# power_PCB_schematic.net
KiCad netlist of a schematic drawn in EAGLE
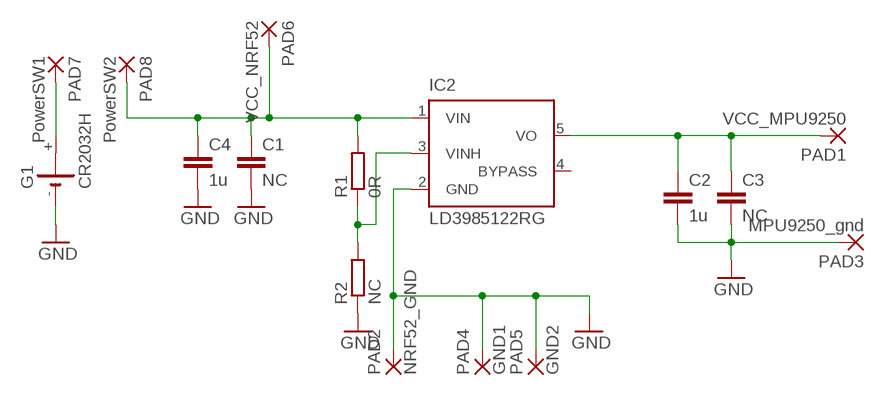
[diagram p0: schematic, sheet 1]

(export (version "E")
  (design (tool "Eeschema 10.0.6"))
  (components
    (comp (ref "C1")
      (value "NC")
      (footprint "eagle-import:C0805")
      (libsource (lib "eagle-import") (part "C-EUC0805"))
    )
    (comp (ref "C2")
      (value "1u")
      (footprint "eagle-import:C0805")
      (libsource (lib "eagle-import") (part "C-EUC0805"))
    )
    (comp (ref "C3")
      (value "NC")
      (footprint "eagle-import:C0805")
      (libsource (lib "eagle-import") (part "C-EUC0805"))
    )
    (comp (ref "C4")
      (value "1u")
      (footprint "eagle-import:C0805")
      (libsource (lib "eagle-import") (part "C-EUC0805"))
    )
    (comp (ref "G1")
      (value "CR2032H")
      (footprint "eagle-import:CR2032H")
      (libsource (lib "eagle-import") (part "CR2032H"))
    )
    (comp (ref "IC2")
      (value "LD3985122RG")
      (footprint "eagle-import:TSOT23-5L")
      (libsource (lib "eagle-import") (part "LD3985G122R"))
    )
    (comp (ref "PAD1")
      (value "VCC_MPU9250")
      (footprint "eagle-import:2,54_1,0")
      (libsource (lib "eagle-import") (part "2,54/1,0"))
    )
    (comp (ref "PAD2")
      (value "NRF52_GND")
      (footprint "eagle-import:2,54_1,0")
      (libsource (lib "eagle-import") (part "2,54/1,0"))
    )
    (comp (ref "PAD3")
      (value "MPU9250_gnd")
      (footprint "eagle-import:2,54_1,0")
      (libsource (lib "eagle-import") (part "2,54/1,0"))
    )
    (comp (ref "PAD4")
      (value "GND1")
      (footprint "eagle-import:2,54_1,0")
      (libsource (lib "eagle-import") (part "2,54/1,0"))
    )
    (comp (ref "PAD5")
      (value "GND2")
      (footprint "eagle-import:2,54_1,0")
      (libsource (lib "eagle-import") (part "2,54/1,0"))
    )
    (comp (ref "PAD6")
      (value "VCC_NRF52")
      (footprint "eagle-import:2,54_1,0")
      (libsource (lib "eagle-import") (part "2,54/1,0"))
    )
    (comp (ref "PAD7")
      (value "PowerSW1")
      (footprint "eagle-import:2,54_1,0")
      (libsource (lib "eagle-import") (part "2,54/1,0"))
    )
    (comp (ref "PAD8")
      (value "PowerSW2")
      (footprint "eagle-import:2,54_1,0")
      (libsource (lib "eagle-import") (part "2,54/1,0"))
    )
    (comp (ref "R1")
      (value "0R")
      (footprint "eagle-import:R1206")
      (libsource (lib "eagle-import") (part "R-EU_R1206"))
    )
    (comp (ref "R2")
      (value "NC")
      (footprint "eagle-import:R0603")
      (libsource (lib "eagle-import") (part "R-EU_R0603"))
    )
  )
  (nets
    (net (code "1") (name "GND") (class "Default")
      (node (ref "C1") (pin "2") (pinfunction "2_2") (pintype "passive"))
      (node (ref "C2") (pin "2") (pinfunction "2_2") (pintype "passive"))
      (node (ref "C3") (pin "2") (pinfunction "2_2") (pintype "passive"))
      (node (ref "C4") (pin "2") (pinfunction "2_2") (pintype "passive"))
      (node (ref "G1") (pin "-") (pinfunction "-_-") (pintype "passive"))
      (node (ref "IC2") (pin "2") (pinfunction "GND_2") (pintype "power_in"))
      (node (ref "PAD2") (pin "1") (pinfunction "P_1") (pintype "passive"))
      (node (ref "PAD3") (pin "1") (pinfunction "P_1") (pintype "passive"))
      (node (ref "PAD4") (pin "1") (pinfunction "P_1") (pintype "passive"))
      (node (ref "PAD5") (pin "1") (pinfunction "P_1") (pintype "passive"))
      (node (ref "R2") (pin "1") (pinfunction "1_1") (pintype "passive"))
    )
    (net (code "2") (name "Net-(IC2-VIN)") (class "Default")
      (node (ref "C1") (pin "1") (pinfunction "1_1") (pintype "passive"))
      (node (ref "C4") (pin "1") (pinfunction "1_1") (pintype "passive"))
      (node (ref "IC2") (pin "1") (pinfunction "VIN_1") (pintype "input"))
      (node (ref "PAD6") (pin "1") (pinfunction "P_1") (pintype "passive"))
      (node (ref "PAD8") (pin "1") (pinfunction "P_1") (pintype "passive"))
      (node (ref "R1") (pin "2") (pinfunction "2_2") (pintype "passive"))
    )
    (net (code "3") (name "Net-(IC2-VINH)") (class "Default")
      (node (ref "IC2") (pin "3") (pinfunction "VINH_3") (pintype "input"))
      (node (ref "R1") (pin "1") (pinfunction "1_1") (pintype "passive"))
      (node (ref "R2") (pin "2") (pinfunction "2_2") (pintype "passive"))
    )
    (net (code "4") (name "Net-(IC2-VO)") (class "Default")
      (node (ref "C2") (pin "1") (pinfunction "1_1") (pintype "passive"))
      (node (ref "C3") (pin "1") (pinfunction "1_1") (pintype "passive"))
      (node (ref "IC2") (pin "5") (pinfunction "VO_5") (pintype "output"))
      (node (ref "PAD1") (pin "1") (pinfunction "P_1") (pintype "passive"))
    )
    (net (code "5") (name "Net-(PAD7-P)") (class "Default")
      (node (ref "G1") (pin "+") (pinfunction "+_+") (pintype "passive"))
      (node (ref "PAD7") (pin "1") (pinfunction "P_1") (pintype "passive"))
    )
    (net (code "6") (name "unconnected-(G1-+-Pad+@1)") (class "Default")
      (node (ref "G1") (pin "+@1") (pinfunction "+_+@1") (pintype "passive"))
    )
    (net (code "7") (name "unconnected-(IC2-BYPASS-Pad4)") (class "Default")
      (node (ref "IC2") (pin "4") (pinfunction "BYPASS_4") (pintype "passive"))
    )
  )
)
